# 468332_031_3_1.net
KiCad netlist of a schematic drawn in Altium Designer
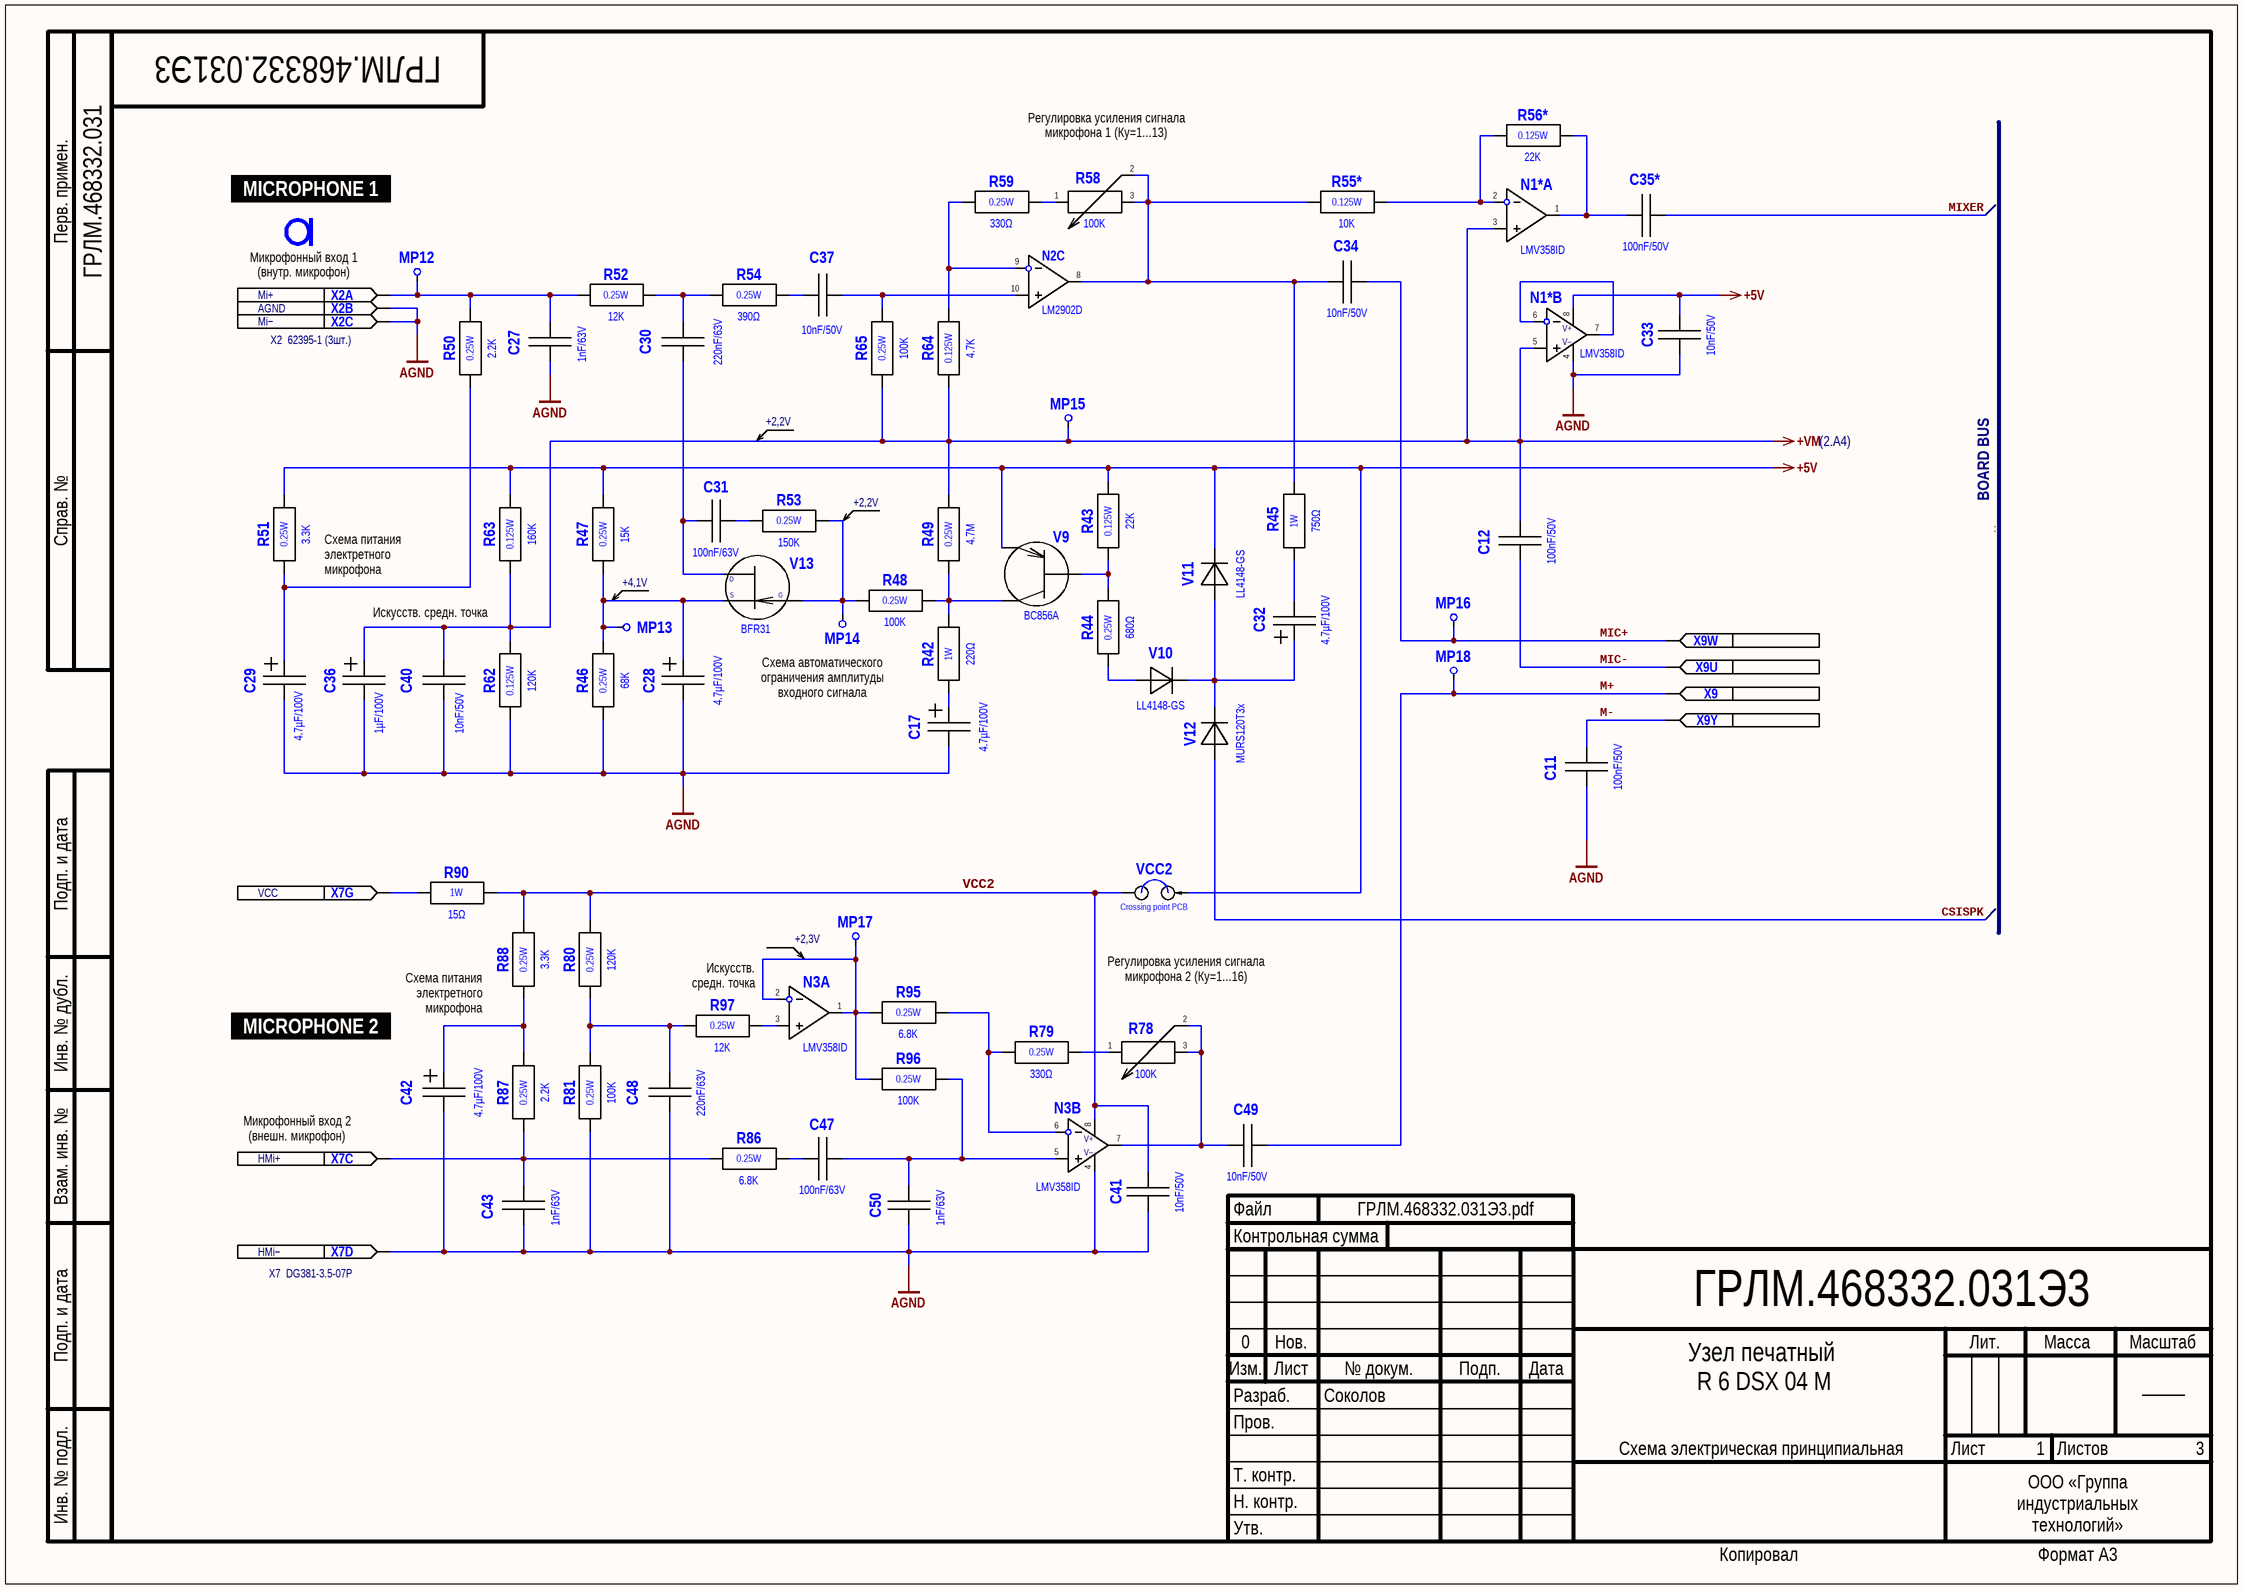
[diagram p0: ГРЛМ.468332.031Э3 (Лист 1).SchDoc]

(export (version "E")
  (design (tool "Eeschema 10.0.6"))
  (components
    (comp (ref "C11")
      (value "100nF/50V")
      (footprint "SMD Capacitor 0805")
      (fields (field (name "PARTNUMBER") "CC0805KRX7R9BB104"))
      (libsource (lib "R 6 DSX 04") (part "Capacitor"))
    )
    (comp (ref "C12")
      (value "100nF/50V")
      (footprint "SMD Capacitor 0805")
      (fields (field (name "PARTNUMBER") "CC0805KRX7R9BB104"))
      (libsource (lib "R 6 DSX 04") (part "Capacitor"))
    )
    (comp (ref "C17")
      (value "4.7µF/100V")
      (footprint "Capacitor  electrolytic 5x11mm")
      (description "Capacitor Electrolytic")
      (fields (field (name "PARTNUMBER") "К50-35-100В-4,7мкФ 5х11мм"))
      (libsource (lib "R 6 DSX 04") (part "Capacitor Electrolytic"))
    )
    (comp (ref "C27")
      (value "1nF/63V")
      (footprint "SMD Capacitor 0805")
      (fields (field (name "PARTNUMBER") "CC0805JRNPO0BN102"))
      (libsource (lib "R 6 DSX 04") (part "Capacitor"))
    )
    (comp (ref "C28")
      (value "4.7µF/100V")
      (footprint "Capacitor  electrolytic 5x11mm")
      (description "Capacitor Electrolytic")
      (fields (field (name "PARTNUMBER") "К50-35-100В-4,7мкФ 5х11мм"))
      (libsource (lib "R 6 DSX 04") (part "Capacitor Electrolytic"))
    )
    (comp (ref "C29")
      (value "4.7µF/100V")
      (footprint "Capacitor  electrolytic 5x11mm")
      (description "Capacitor Electrolytic")
      (fields (field (name "PARTNUMBER") "К50-35-100В-4,7мкФ 5х11мм"))
      (libsource (lib "R 6 DSX 04") (part "Capacitor Electrolytic"))
    )
    (comp (ref "C30")
      (value "220nF/63V")
      (footprint "SMD Capacitor 0805")
      (fields (field (name "PARTNUMBER") "GRM31MR72A224KA01L"))
      (libsource (lib "R 6 DSX 04") (part "Capacitor"))
    )
    (comp (ref "C31")
      (value "100nF/63V")
      (footprint "SMD Capacitor 0805")
      (fields (field (name "PARTNUMBER") "CC0805KRX7R9BB104"))
      (libsource (lib "R 6 DSX 04") (part "Capacitor"))
    )
    (comp (ref "C32")
      (value "4.7µF/100V")
      (footprint "Capacitor  electrolytic 5x11mm")
      (description "Capacitor Electrolytic")
      (fields (field (name "PARTNUMBER") "К50-35-100В-4,7мкФ 5х11мм"))
      (libsource (lib "R 6 DSX 04") (part "Capacitor Electrolytic"))
    )
    (comp (ref "C33")
      (value "10nF/50V")
      (footprint "SMD Capacitor 0805")
      (fields (field (name "PARTNUMBER") "CC0805KRX7R9BB103"))
      (libsource (lib "R 6 DSX 04") (part "Capacitor"))
    )
    (comp (ref "C34")
      (value "10nF/50V")
      (footprint "SMD Capacitor 0805")
      (fields (field (name "PARTNUMBER") "CC0805KRX7R9BB103"))
      (libsource (lib "R 6 DSX 04") (part "Capacitor"))
    )
    (comp (ref "C35*")
      (value "100nF/50V")
      (footprint "SMD Capacitor 0805")
      (fields (field (name "PARTNUMBER") "CC0805KRX7R9BB104"))
      (libsource (lib "R 6 DSX 04") (part "Capacitor"))
    )
    (comp (ref "C36")
      (value "1µF/100V")
      (footprint "Capacitor  electrolytic 5x11mm")
      (description "Capacitor Electrolytic")
      (fields (field (name "PARTNUMBER") "К50-35-100В-1мкФ 5х11мм"))
      (libsource (lib "R 6 DSX 04") (part "Capacitor Electrolytic"))
    )
    (comp (ref "C37")
      (value "10nF/50V")
      (footprint "SMD Capacitor 0805")
      (fields (field (name "PARTNUMBER") "CC0805KRX7R9BB103"))
      (libsource (lib "R 6 DSX 04") (part "Capacitor"))
    )
    (comp (ref "C40")
      (value "10nF/50V")
      (footprint "SMD Capacitor 0805")
      (fields (field (name "PARTNUMBER") "CC0805KRX7R9BB103"))
      (libsource (lib "R 6 DSX 04") (part "Capacitor"))
    )
    (comp (ref "C41")
      (value "10nF/50V")
      (footprint "SMD Capacitor 0805")
      (fields (field (name "PARTNUMBER") "CC0805KRX7R9BB103"))
      (libsource (lib "R 6 DSX 04") (part "Capacitor"))
    )
    (comp (ref "C42")
      (value "4.7µF/100V")
      (footprint "Capacitor  electrolytic 5x11mm")
      (description "Capacitor Electrolytic")
      (fields (field (name "PARTNUMBER") "К50-35-100В-4,7мкФ 5х11мм"))
      (libsource (lib "R 6 DSX 04") (part "Capacitor Electrolytic"))
    )
    (comp (ref "C43")
      (value "1nF/63V")
      (footprint "SMD Capacitor 0805")
      (fields (field (name "PARTNUMBER") "CC0805JRNPO0BN102"))
      (libsource (lib "R 6 DSX 04") (part "Capacitor"))
    )
    (comp (ref "C47")
      (value "100nF/63V")
      (footprint "SMD Capacitor 0805")
      (fields (field (name "PARTNUMBER") "CC1206KKX7R0BB104"))
      (libsource (lib "R 6 DSX 04") (part "Capacitor"))
    )
    (comp (ref "C48")
      (value "220nF/63V")
      (footprint "SMD Capacitor 0805")
      (fields (field (name "PARTNUMBER") "GRM31MR72A224KA01L"))
      (libsource (lib "R 6 DSX 04") (part "Capacitor"))
    )
    (comp (ref "C49")
      (value "10nF/50V")
      (footprint "SMD Capacitor 0805")
      (fields (field (name "PARTNUMBER") "CC0805KRX7R9BB103"))
      (libsource (lib "R 6 DSX 04") (part "Capacitor"))
    )
    (comp (ref "C50")
      (value "1nF/63V")
      (footprint "SMD Capacitor 0805")
      (fields (field (name "PARTNUMBER") "CC0805JRNPO0BN102"))
      (libsource (lib "R 6 DSX 04") (part "Capacitor"))
    )
    (comp (ref "MP12")
      (value "TestPoint SMD")
      (footprint "Test point SMD")
      (description "SMD Test Point")
      (libsource (lib "R 1 DTS 011") (part "TestPoint SMD"))
    )
    (comp (ref "MP13")
      (value "TestPoint SMD")
      (footprint "Test point SMD")
      (description "SMD Test Point")
      (libsource (lib "R 1 DTS 011") (part "TestPoint SMD"))
    )
    (comp (ref "MP14")
      (value "TestPoint SMD")
      (footprint "Test point SMD")
      (description "SMD Test Point")
      (libsource (lib "R 1 DTS 011") (part "TestPoint SMD"))
    )
    (comp (ref "MP15")
      (value "TestPoint SMD")
      (footprint "Test point SMD")
      (description "SMD Test Point")
      (libsource (lib "R 1 DTS 011") (part "TestPoint SMD"))
    )
    (comp (ref "MP16")
      (value "TestPoint SMD")
      (footprint "Test point SMD")
      (description "SMD Test Point")
      (libsource (lib "R 1 DTS 011") (part "TestPoint SMD"))
    )
    (comp (ref "MP17")
      (value "TestPoint SMD")
      (footprint "Test point SMD")
      (description "SMD Test Point")
      (libsource (lib "R 1 DTS 011") (part "TestPoint SMD"))
    )
    (comp (ref "MP18")
      (value "TestPoint SMD")
      (footprint "Test point SMD")
      (description "SMD Test Point")
      (libsource (lib "R 1 DTS 011") (part "TestPoint SMD"))
    )
    (comp (ref "N1*")
      (value "LMV358ID")
      (footprint "SO8 (SOIC-8)")
      (description "Low-power dual operational amplifiers\r\nSO-14")
      (libsource (lib "R 6 DSX 04") (part "LMV358D"))
    )
    (comp (ref "N2")
      (value "LM2902D")
      (footprint "SO14")
      (description "Low-power quad operational amplifiers\r\nSO-14")
      (fields (field (name "PARTNUMBER") "LM2902D(DT)"))
      (libsource (lib "R 6 DSX 04") (part "LM2902D(DT)"))
    )
    (comp (ref "N3")
      (value "LMV358ID")
      (footprint "SO8 (SOIC-8)")
      (description "Low-power dual operational amplifiers\r\nSO-14")
      (libsource (lib "R 6 DSX 04") (part "LMV358D"))
    )
    (comp (ref "R42")
      (value "220Ω")
      (footprint "Resistor FMP100 1W Yageo")
      (fields (field (name "PARTNUMBER") "FMP100JR-52-220R") (field (name "POWER DISSIPATION") "1W"))
      (libsource (lib "R 6 DSX 04") (part "Resistor"))
    )
    (comp (ref "R43")
      (value "22K")
      (footprint "SMD Resistor 0805")
      (fields (field (name "PARTNUMBER") "RC0805JR-0722KL") (field (name "POWER DISSIPATION") "0.125W"))
      (libsource (lib "R 6 DSX 04") (part "Resistor"))
    )
    (comp (ref "R44")
      (value "680Ω")
      (footprint "SMD Resistor 1206")
      (fields (field (name "PARTNUMBER") "RC1206JR-07680RL") (field (name "POWER DISSIPATION") "0.25W"))
      (libsource (lib "R 6 DSX 04") (part "Resistor"))
    )
    (comp (ref "R45")
      (value "750Ω")
      (footprint "Resistor FMP100 1W Yageo")
      (fields (field (name "PARTNUMBER") "FMP100JR-52-750R") (field (name "POWER DISSIPATION") "1W"))
      (libsource (lib "R 6 DSX 04") (part "Resistor"))
    )
    (comp (ref "R46")
      (value "68K")
      (footprint "SMD Resistor 1206")
      (fields (field (name "PARTNUMBER") "RC1206JR-0768KL") (field (name "POWER DISSIPATION") "0.25W"))
      (libsource (lib "R 6 DSX 04") (part "Resistor"))
    )
    (comp (ref "R47")
      (value "15K")
      (footprint "SMD Resistor 1206")
      (fields (field (name "PARTNUMBER") "RC1206JR-0715KL") (field (name "POWER DISSIPATION") "0.25W"))
      (libsource (lib "R 6 DSX 04") (part "Resistor"))
    )
    (comp (ref "R48")
      (value "100K")
      (footprint "SMD Resistor 1206")
      (fields (field (name "PARTNUMBER") "RC1206JR-07100KL") (field (name "POWER DISSIPATION") "0.25W"))
      (libsource (lib "R 6 DSX 04") (part "Resistor"))
    )
    (comp (ref "R49")
      (value "4.7M")
      (footprint "SMD Resistor 1206")
      (fields (field (name "PARTNUMBER") "RC1206JR-074M7L") (field (name "POWER DISSIPATION") "0.25W"))
      (libsource (lib "R 6 DSX 04") (part "Resistor"))
    )
    (comp (ref "R50")
      (value "2.2K")
      (footprint "SMD Resistor 1206")
      (fields (field (name "PARTNUMBER") "RC1206JR-072K2L") (field (name "POWER DISSIPATION") "0.25W"))
      (libsource (lib "R 6 DSX 04") (part "Resistor"))
    )
    (comp (ref "R51")
      (value "3.3K")
      (footprint "SMD Resistor 1206")
      (fields (field (name "PARTNUMBER") "RC1206JR-073K3L") (field (name "POWER DISSIPATION") "0.25W"))
      (libsource (lib "R 6 DSX 04") (part "Resistor"))
    )
    (comp (ref "R52")
      (value "12K")
      (footprint "SMD Resistor 1206")
      (fields (field (name "PARTNUMBER") "RC1206JR-0712KL") (field (name "POWER DISSIPATION") "0.25W"))
      (libsource (lib "R 6 DSX 04") (part "Resistor"))
    )
    (comp (ref "R53")
      (value "150K")
      (footprint "SMD Resistor 1206")
      (fields (field (name "PARTNUMBER") "RC1206JR-07150KL") (field (name "POWER DISSIPATION") "0.25W"))
      (libsource (lib "R 6 DSX 04") (part "Resistor"))
    )
    (comp (ref "R54")
      (value "390Ω")
      (footprint "SMD Resistor 1206")
      (fields (field (name "PARTNUMBER") "RC1206JR-07390RL") (field (name "POWER DISSIPATION") "0.25W"))
      (libsource (lib "R 6 DSX 04") (part "Resistor"))
    )
    (comp (ref "R55*")
      (value "10K")
      (footprint "SMD Resistor 0805")
      (fields (field (name "PARTNUMBER") "RC0805JR-0710KL") (field (name "POWER DISSIPATION") "0.125W"))
      (libsource (lib "R 6 DSX 04") (part "Resistor"))
    )
    (comp (ref "R56*")
      (value "22K")
      (footprint "SMD Resistor 0805")
      (fields (field (name "PARTNUMBER") "RC0805JR-0722KL") (field (name "POWER DISSIPATION") "0.125W"))
      (libsource (lib "R 6 DSX 04") (part "Resistor"))
    )
    (comp (ref "R58")
      (value "100K")
      (footprint "3362H Square Trimming Potentiometer")
      (fields (field (name "PARTNUMBER") "3362H-1-104LF"))
      (libsource (lib "R 6 DSX 04") (part "Resistor adjustable"))
    )
    (comp (ref "R59")
      (value "330Ω")
      (footprint "SMD Resistor 1206")
      (fields (field (name "PARTNUMBER") "RC1206JR-07330RL") (field (name "POWER DISSIPATION") "0.25W"))
      (libsource (lib "R 6 DSX 04") (part "Resistor"))
    )
    (comp (ref "R62")
      (value "120K")
      (footprint "SMD Resistor 0805")
      (fields (field (name "PARTNUMBER") "RC0805FR-07120KL") (field (name "POWER DISSIPATION") "0.125W"))
      (libsource (lib "R 6 DSX 04") (part "Resistor"))
    )
    (comp (ref "R63")
      (value "160K")
      (footprint "SMD Resistor 0805")
      (fields (field (name "PARTNUMBER") "RC0805FR-07160KL") (field (name "POWER DISSIPATION") "0.125W"))
      (libsource (lib "R 6 DSX 04") (part "Resistor"))
    )
    (comp (ref "R64")
      (value "4.7K")
      (footprint "SMD Resistor 0805")
      (fields (field (name "PARTNUMBER") "RC0805JR-074K7L") (field (name "POWER DISSIPATION") "0.125W"))
      (libsource (lib "R 6 DSX 04") (part "Resistor"))
    )
    (comp (ref "R65")
      (value "100K")
      (footprint "SMD Resistor 1206")
      (fields (field (name "PARTNUMBER") "RC1206JR-07100KL") (field (name "POWER DISSIPATION") "0.25W"))
      (libsource (lib "R 6 DSX 04") (part "Resistor"))
    )
    (comp (ref "R78")
      (value "100K")
      (footprint "3362H Square Trimming Potentiometer")
      (fields (field (name "PARTNUMBER") "3362H-1-104LF"))
      (libsource (lib "R 6 DSX 04") (part "Resistor adjustable"))
    )
    (comp (ref "R79")
      (value "330Ω")
      (footprint "SMD Resistor 1206")
      (fields (field (name "PARTNUMBER") "RC1206JR-07330RL") (field (name "POWER DISSIPATION") "0.25W"))
      (libsource (lib "R 6 DSX 04") (part "Resistor"))
    )
    (comp (ref "R80")
      (value "120K")
      (footprint "SMD Resistor 1206")
      (fields (field (name "PARTNUMBER") "RC1206JR-07120KL") (field (name "POWER DISSIPATION") "0.25W"))
      (libsource (lib "R 6 DSX 04") (part "Resistor"))
    )
    (comp (ref "R81")
      (value "100K")
      (footprint "SMD Resistor 1206")
      (fields (field (name "PARTNUMBER") "RC1206JR-07100KL") (field (name "POWER DISSIPATION") "0.25W"))
      (libsource (lib "R 6 DSX 04") (part "Resistor"))
    )
    (comp (ref "R86")
      (value "6.8K")
      (footprint "SMD Resistor 1206")
      (fields (field (name "PARTNUMBER") "RC1206JR-076K8L") (field (name "POWER DISSIPATION") "0.25W"))
      (libsource (lib "R 6 DSX 04") (part "Resistor"))
    )
    (comp (ref "R87")
      (value "2.2K")
      (footprint "SMD Resistor 1206")
      (fields (field (name "PARTNUMBER") "RC1206JR-072K2L") (field (name "POWER DISSIPATION") "0.25W"))
      (libsource (lib "R 6 DSX 04") (part "Resistor"))
    )
    (comp (ref "R88")
      (value "3.3K")
      (footprint "SMD Resistor 1206")
      (fields (field (name "PARTNUMBER") "RC1206JR-073K3L") (field (name "POWER DISSIPATION") "0.25W"))
      (libsource (lib "R 6 DSX 04") (part "Resistor"))
    )
    (comp (ref "R90")
      (value "15Ω")
      (footprint "Resistor FMP100 1W Yageo")
      (fields (field (name "PARTNUMBER") "FMP100JT-52-15R") (field (name "POWER DISSIPATION") "1W"))
      (libsource (lib "R 6 DSX 04") (part "Resistor"))
    )
    (comp (ref "R95")
      (value "6.8K")
      (footprint "SMD Resistor 1206")
      (fields (field (name "PARTNUMBER") "RC1206JR-076K8L") (field (name "POWER DISSIPATION") "0.25W"))
      (libsource (lib "R 6 DSX 04") (part "Resistor"))
    )
    (comp (ref "R96")
      (value "100K")
      (footprint "SMD Resistor 1206")
      (fields (field (name "PARTNUMBER") "RC1206JR-07100KL") (field (name "POWER DISSIPATION") "0.25W"))
      (libsource (lib "R 6 DSX 04") (part "Resistor"))
    )
    (comp (ref "R97")
      (value "12K")
      (footprint "SMD Resistor 1206")
      (fields (field (name "PARTNUMBER") "RC1206JR-0712KL") (field (name "POWER DISSIPATION") "0.25W"))
      (libsource (lib "R 6 DSX 04") (part "Resistor"))
    )
    (comp (ref "V9")
      (value "BC856A")
      (footprint "Transistor BC856 SOT23 (PNP transistor)")
      (description "Base - 1, Emitter - 2, Collector - 3")
      (libsource (lib "R 6 DSX 04") (part "Transistor PNP"))
    )
    (comp (ref "V10")
      (value "LL4148-GS")
      (footprint "Diode SOD80C (Anode pin 1)")
      (description "LL4148-GS MELF Package")
      (fields (field (name "PARTNUMBER") "LL4148-GSxx"))
      (libsource (lib "R 6 DSX 04") (part "Diode"))
    )
    (comp (ref "V11")
      (value "LL4148-GS")
      (footprint "Diode SOD80C (Anode pin 1)")
      (description "LL4148-GS MELF Package")
      (fields (field (name "PARTNUMBER") "LL4148-GSxx"))
      (libsource (lib "R 6 DSX 04") (part "Diode"))
    )
    (comp (ref "V12")
      (value "MURS120T3x")
      (footprint "Diode SMB (DO-214AA)")
      (description "LL4148-GS MELF Package")
      (libsource (lib "R 6 DSX 04") (part "Diode"))
    )
    (comp (ref "V13")
      (value "BFR31")
      (footprint "Transistor BFR31 SOT23 (FET N-channel)")
      (description "Drain - 1, Source - 2, Gate - 3")
      (libsource (lib "R 6 DSX 04") (part "Transistor FET N-channel"))
    )
    (comp (ref "VCC2")
      (value "Crossing point PCB")
      (footprint "Crossing point PCB")
      (description "Crossing point")
      (libsource (lib "R 6 DSX 04") (part "Crossing point PCB"))
    )
    (comp (ref "X2")
      (value "62395-1 (3ps)")
      (footprint "Faston Connector 3 x 2.8 mm")
      (fields (field (name "PARTNUMBER") "62395-1 (3 ps)"))
      (libsource (lib "R 6 DSX 04") (part "Connector 3 pins (universal)"))
    )
    (comp (ref "X7")
      (value "DG381-3.5-07P")
      (footprint "DG381-3.5-07P Terminals")
      (libsource (lib "R 6 DSX 04") (part "Connector 7 pins (universal)"))
    )
    (comp (ref "X9")
      (value "5177983-2")
      (footprint "Connector 5177983-2")
      (libsource (lib "R 6 DSX 04") (part "Connector 60 pins (universal)"))
    )
  )
  (nets
    (net (code "2") (name "+5V") (class "Default")
      (node (ref "C33") (pin "2") (pinfunction "2_2") (pintype "passive"))
      (node (ref "N1*") (pin "8") (pintype "passive"))
      (node (ref "R43") (pin "2") (pinfunction "2_2") (pintype "passive"))
      (node (ref "R47") (pin "2") (pinfunction "2_2") (pintype "passive"))
      (node (ref "R51") (pin "2") (pinfunction "2_2") (pintype "passive"))
      (node (ref "R63") (pin "2") (pinfunction "2_2") (pintype "passive"))
      (node (ref "V11") (pin "2") (pinfunction "2_2") (pintype "passive"))
      (node (ref "V9") (pin "2") (pinfunction "Emitter_2") (pintype "passive"))
      (node (ref "VCC2") (pin "1") (pinfunction "1_1") (pintype "passive"))
    )
    (net (code "3") (name "+VM") (class "Default")
      (node (ref "C12") (pin "2") (pinfunction "2_2") (pintype "passive"))
      (node (ref "C36") (pin "1") (pinfunction "1_1") (pintype "passive"))
      (node (ref "C40") (pin "2") (pinfunction "2_2") (pintype "passive"))
      (node (ref "MP15") (pin "1") (pinfunction "1_1") (pintype "passive"))
      (node (ref "N1*") (pin "3") (pintype "passive"))
      (node (ref "N1*") (pin "5") (pintype "passive"))
      (node (ref "R49") (pin "2") (pinfunction "2_2") (pintype "passive"))
      (node (ref "R62") (pin "2") (pinfunction "2_2") (pintype "passive"))
      (node (ref "R63") (pin "1") (pinfunction "1_1") (pintype "passive"))
      (node (ref "R64") (pin "1") (pinfunction "1_1") (pintype "passive"))
      (node (ref "R65") (pin "1") (pinfunction "1_1") (pintype "passive"))
    )
    (net (code "4") (name "/CSISPK") (class "Default")
      (node (ref "V12") (pin "1") (pinfunction "1_1") (pintype "passive"))
    )
    (net (code "5") (name "/M+") (class "Default")
      (node (ref "C49") (pin "2") (pinfunction "2_2") (pintype "passive"))
      (node (ref "MP18") (pin "1") (pinfunction "1_1") (pintype "passive"))
      (node (ref "X9") (pin "27") (pinfunction "27_27") (pintype "passive"))
    )
    (net (code "6") (name "/M-") (class "Default")
      (node (ref "C11") (pin "2") (pinfunction "2_2") (pintype "passive"))
      (node (ref "X9") (pin "25") (pinfunction "25_25") (pintype "passive"))
    )
    (net (code "7") (name "/MIC+") (class "Default")
      (node (ref "C34") (pin "2") (pinfunction "2_2") (pintype "passive"))
      (node (ref "MP16") (pin "1") (pinfunction "1_1") (pintype "passive"))
      (node (ref "X9") (pin "23") (pinfunction "23_23") (pintype "passive"))
    )
    (net (code "8") (name "/MIC-") (class "Default")
      (node (ref "C12") (pin "1") (pinfunction "1_1") (pintype "passive"))
      (node (ref "X9") (pin "21") (pinfunction "21_21") (pintype "passive"))
    )
    (net (code "9") (name "/MIXER") (class "Default")
      (node (ref "C35*") (pin "2") (pinfunction "2_2") (pintype "passive"))
    )
    (net (code "10") (name "/VCC2") (class "Default")
      (node (ref "C41") (pin "2") (pinfunction "2_2") (pintype "passive"))
      (node (ref "N3") (pin "8") (pintype "passive"))
      (node (ref "R80") (pin "2") (pinfunction "2_2") (pintype "passive"))
      (node (ref "R88") (pin "2") (pinfunction "2_2") (pintype "passive"))
      (node (ref "R90") (pin "2") (pinfunction "2_2") (pintype "passive"))
      (node (ref "VCC2") (pin "2") (pinfunction "2_2") (pintype "passive"))
    )
    (net (code "12") (name "AGND") (class "Default")
      (node (ref "C11") (pin "1") (pinfunction "1_1") (pintype "passive"))
      (node (ref "C17") (pin "2") (pinfunction "2_2") (pintype "passive"))
      (node (ref "C27") (pin "1") (pinfunction "1_1") (pintype "passive"))
      (node (ref "C28") (pin "2") (pinfunction "2_2") (pintype "passive"))
      (node (ref "C29") (pin "2") (pinfunction "2_2") (pintype "passive"))
      (node (ref "C33") (pin "1") (pinfunction "1_1") (pintype "passive"))
      (node (ref "C36") (pin "2") (pinfunction "2_2") (pintype "passive"))
      (node (ref "C40") (pin "1") (pinfunction "1_1") (pintype "passive"))
      (node (ref "C41") (pin "1") (pinfunction "1_1") (pintype "passive"))
      (node (ref "C42") (pin "2") (pinfunction "2_2") (pintype "passive"))
      (node (ref "C43") (pin "1") (pinfunction "1_1") (pintype "passive"))
      (node (ref "C48") (pin "1") (pinfunction "1_1") (pintype "passive"))
      (node (ref "C50") (pin "1") (pinfunction "1_1") (pintype "passive"))
      (node (ref "N1*") (pin "4") (pintype "passive"))
      (node (ref "N3") (pin "4") (pintype "passive"))
      (node (ref "R46") (pin "1") (pinfunction "1_1") (pintype "passive"))
      (node (ref "R62") (pin "1") (pinfunction "1_1") (pintype "passive"))
      (node (ref "R81") (pin "1") (pinfunction "1_1") (pintype "passive"))
      (node (ref "X2") (pin "2") (pinfunction "2_2") (pintype "passive"))
      (node (ref "X2") (pin "3") (pinfunction "3_3") (pintype "passive"))
      (node (ref "X7") (pin "4") (pinfunction "4_4") (pintype "passive"))
    )
    (net (code "13") (name "Net-(C17-Pad1)") (class "Default")
      (node (ref "C17") (pin "1") (pinfunction "1_1") (pintype "passive"))
      (node (ref "R42") (pin "1") (pinfunction "1_1") (pintype "passive"))
    )
    (net (code "14") (name "Net-(C27-Pad2)") (class "Default")
      (node (ref "C27") (pin "2") (pinfunction "2_2") (pintype "passive"))
      (node (ref "MP12") (pin "1") (pinfunction "1_1") (pintype "passive"))
      (node (ref "R50") (pin "2") (pinfunction "2_2") (pintype "passive"))
      (node (ref "R52") (pin "1") (pinfunction "1_1") (pintype "passive"))
      (node (ref "X2") (pin "1") (pinfunction "1_1") (pintype "passive"))
    )
    (net (code "15") (name "Net-(C29-Pad1)") (class "Default")
      (node (ref "C29") (pin "1") (pinfunction "1_1") (pintype "passive"))
      (node (ref "R50") (pin "1") (pinfunction "1_1") (pintype "passive"))
      (node (ref "R51") (pin "1") (pinfunction "1_1") (pintype "passive"))
    )
    (net (code "16") (name "Net-(C30-Pad2)") (class "Default")
      (node (ref "C30") (pin "2") (pinfunction "2_2") (pintype "passive"))
      (node (ref "R52") (pin "2") (pinfunction "2_2") (pintype "passive"))
      (node (ref "R54") (pin "1") (pinfunction "1_1") (pintype "passive"))
    )
    (net (code "17") (name "Net-(C31-Pad1)") (class "Default")
      (node (ref "C31") (pin "1") (pinfunction "1_1") (pintype "passive"))
      (node (ref "R53") (pin "1") (pinfunction "1_1") (pintype "passive"))
    )
    (net (code "18") (name "Net-(C32-Pad1)") (class "Default")
      (node (ref "C32") (pin "1") (pinfunction "1_1") (pintype "passive"))
      (node (ref "V10") (pin "2") (pinfunction "2_2") (pintype "passive"))
      (node (ref "V11") (pin "1") (pinfunction "1_1") (pintype "passive"))
      (node (ref "V12") (pin "2") (pinfunction "2_2") (pintype "passive"))
    )
    (net (code "19") (name "Net-(C32-Pad2)") (class "Default")
      (node (ref "C32") (pin "2") (pinfunction "2_2") (pintype "passive"))
      (node (ref "R45") (pin "2") (pinfunction "2_2") (pintype "passive"))
    )
    (net (code "20") (name "Net-(C34-Pad1)") (class "Default")
      (node (ref "C34") (pin "1") (pinfunction "1_1") (pintype "passive"))
      (node (ref "N2") (pin "8") (pintype "passive"))
      (node (ref "R45") (pin "1") (pinfunction "1_1") (pintype "passive"))
      (node (ref "R55*") (pin "1") (pinfunction "1_1") (pintype "passive"))
      (node (ref "R58") (pin "2") (pinfunction "2_2") (pintype "passive"))
      (node (ref "R58") (pin "3") (pinfunction "3_3") (pintype "passive"))
    )
    (net (code "21") (name "Net-(C35*-Pad1)") (class "Default")
      (node (ref "C35*") (pin "1") (pinfunction "1_1") (pintype "passive"))
      (node (ref "N1*") (pin "1") (pintype "passive"))
      (node (ref "R56*") (pin "2") (pinfunction "2_2") (pintype "passive"))
    )
    (net (code "22") (name "Net-(C37-Pad1)") (class "Default")
      (node (ref "C37") (pin "1") (pinfunction "1_1") (pintype "passive"))
      (node (ref "R54") (pin "2") (pinfunction "2_2") (pintype "passive"))
    )
    (net (code "23") (name "Net-(C37-Pad2)") (class "Default")
      (node (ref "C37") (pin "2") (pinfunction "2_2") (pintype "passive"))
      (node (ref "N2") (pin "10") (pintype "passive"))
      (node (ref "R65") (pin "2") (pinfunction "2_2") (pintype "passive"))
    )
    (net (code "24") (name "Net-(C42-Pad1)") (class "Default")
      (node (ref "C42") (pin "1") (pinfunction "1_1") (pintype "passive"))
      (node (ref "R87") (pin "2") (pinfunction "2_2") (pintype "passive"))
      (node (ref "R88") (pin "1") (pinfunction "1_1") (pintype "passive"))
    )
    (net (code "25") (name "Net-(C43-Pad2)") (class "Default")
      (node (ref "C43") (pin "2") (pinfunction "2_2") (pintype "passive"))
      (node (ref "R86") (pin "1") (pinfunction "1_1") (pintype "passive"))
      (node (ref "R87") (pin "1") (pinfunction "1_1") (pintype "passive"))
      (node (ref "X7") (pin "3") (pinfunction "3_3") (pintype "passive"))
    )
    (net (code "26") (name "Net-(C47-Pad1)") (class "Default")
      (node (ref "C47") (pin "1") (pinfunction "1_1") (pintype "passive"))
      (node (ref "C50") (pin "2") (pinfunction "2_2") (pintype "passive"))
      (node (ref "N3") (pin "5") (pintype "passive"))
      (node (ref "R96") (pin "2") (pinfunction "2_2") (pintype "passive"))
    )
    (net (code "27") (name "Net-(C47-Pad2)") (class "Default")
      (node (ref "C47") (pin "2") (pinfunction "2_2") (pintype "passive"))
      (node (ref "R86") (pin "2") (pinfunction "2_2") (pintype "passive"))
    )
    (net (code "28") (name "Net-(C48-Pad2)") (class "Default")
      (node (ref "C48") (pin "2") (pinfunction "2_2") (pintype "passive"))
      (node (ref "R80") (pin "1") (pinfunction "1_1") (pintype "passive"))
      (node (ref "R81") (pin "2") (pinfunction "2_2") (pintype "passive"))
      (node (ref "R97") (pin "1") (pinfunction "1_1") (pintype "passive"))
    )
    (net (code "29") (name "Net-(C49-Pad1)") (class "Default")
      (node (ref "C49") (pin "1") (pinfunction "1_1") (pintype "passive"))
      (node (ref "N3") (pin "7") (pintype "passive"))
      (node (ref "R78") (pin "2") (pinfunction "2_2") (pintype "passive"))
      (node (ref "R78") (pin "3") (pinfunction "3_3") (pintype "passive"))
    )
    (net (code "30") (name "Net-(MP17-Pad1)") (class "Default")
      (node (ref "MP17") (pin "1") (pinfunction "1_1") (pintype "passive"))
      (node (ref "N3") (pin "1") (pintype "passive"))
      (node (ref "N3") (pin "2") (pintype "passive"))
      (node (ref "R95") (pin "1") (pinfunction "1_1") (pintype "passive"))
      (node (ref "R96") (pin "1") (pinfunction "1_1") (pintype "passive"))
    )
    (net (code "31") (name "Net-(N1*-Pad2)") (class "Default")
      (node (ref "N1*") (pin "2") (pintype "passive"))
      (node (ref "R55*") (pin "2") (pinfunction "2_2") (pintype "passive"))
      (node (ref "R56*") (pin "1") (pinfunction "1_1") (pintype "passive"))
    )
    (net (code "32") (name "Net-(N1*-Pad6)") (class "Default")
      (node (ref "N1*") (pin "6") (pintype "passive"))
      (node (ref "N1*") (pin "7") (pintype "passive"))
    )
    (net (code "33") (name "Net-(N2-Pad9)") (class "Default")
      (node (ref "N2") (pin "9") (pintype "passive"))
      (node (ref "R59") (pin "1") (pinfunction "1_1") (pintype "passive"))
      (node (ref "R64") (pin "2") (pinfunction "2_2") (pintype "passive"))
    )
    (net (code "34") (name "Net-(N3-Pad3)") (class "Default")
      (node (ref "N3") (pin "3") (pintype "passive"))
      (node (ref "R97") (pin "2") (pinfunction "2_2") (pintype "passive"))
    )
    (net (code "35") (name "Net-(N3-Pad6)") (class "Default")
      (node (ref "N3") (pin "6") (pintype "passive"))
      (node (ref "R79") (pin "1") (pinfunction "1_1") (pintype "passive"))
      (node (ref "R95") (pin "2") (pinfunction "2_2") (pintype "passive"))
    )
    (net (code "36") (name "Net-(R44-Pad1)") (class "Default")
      (node (ref "R44") (pin "1") (pinfunction "1_1") (pintype "passive"))
      (node (ref "V10") (pin "1") (pinfunction "1_1") (pintype "passive"))
    )
    (net (code "37") (name "Net-(R58-Pad1)") (class "Default")
      (node (ref "R58") (pin "1") (pinfunction "1_1") (pintype "passive"))
      (node (ref "R59") (pin "2") (pinfunction "2_2") (pintype "passive"))
    )
    (net (code "38") (name "Net-(R78-Pad1)") (class "Default")
      (node (ref "R78") (pin "1") (pinfunction "1_1") (pintype "passive"))
      (node (ref "R79") (pin "2") (pinfunction "2_2") (pintype "passive"))
    )
    (net (code "39") (name "Net-(R90-Pad1)") (class "Default")
      (node (ref "R90") (pin "1") (pinfunction "1_1") (pintype "passive"))
      (node (ref "X7") (pin "7") (pinfunction "7_7") (pintype "passive"))
    )
    (net (code "40") (name "Net-(V9-Base)") (class "Default")
      (node (ref "R43") (pin "1") (pinfunction "1_1") (pintype "passive"))
      (node (ref "R44") (pin "2") (pinfunction "2_2") (pintype "passive"))
      (node (ref "V9") (pin "1") (pinfunction "Base_1") (pintype "passive"))
    )
    (net (code "41") (name "Net-(V9-Collector)") (class "Default")
      (node (ref "R42") (pin "2") (pinfunction "2_2") (pintype "passive"))
      (node (ref "R48") (pin "2") (pinfunction "2_2") (pintype "passive"))
      (node (ref "R49") (pin "1") (pinfunction "1_1") (pintype "passive"))
      (node (ref "V9") (pin "3") (pinfunction "Collector_3") (pintype "passive"))
    )
    (net (code "42") (name "Net-(V13-Drain)") (class "Default")
      (node (ref "C30") (pin "1") (pinfunction "1_1") (pintype "passive"))
      (node (ref "C31") (pin "2") (pinfunction "2_2") (pintype "passive"))
      (node (ref "V13") (pin "1") (pinfunction "Drain_1") (pintype "passive"))
    )
    (net (code "43") (name "Net-(V13-Gate)") (class "Default")
      (node (ref "MP14") (pin "1") (pinfunction "1_1") (pintype "passive"))
      (node (ref "R48") (pin "1") (pinfunction "1_1") (pintype "passive"))
      (node (ref "R53") (pin "2") (pinfunction "2_2") (pintype "passive"))
      (node (ref "V13") (pin "3") (pinfunction "Gate_3") (pintype "passive"))
    )
    (net (code "44") (name "Net-(V13-Source)") (class "Default")
      (node (ref "C28") (pin "1") (pinfunction "1_1") (pintype "passive"))
      (node (ref "MP13") (pin "1") (pinfunction "1_1") (pintype "passive"))
      (node (ref "R46") (pin "2") (pinfunction "2_2") (pintype "passive"))
      (node (ref "R47") (pin "1") (pinfunction "1_1") (pintype "passive"))
      (node (ref "V13") (pin "2") (pinfunction "Source_2") (pintype "passive"))
    )
  )
)
